# J65VIA.net
KiCad netlist of a schematic drawn in Altium Designer
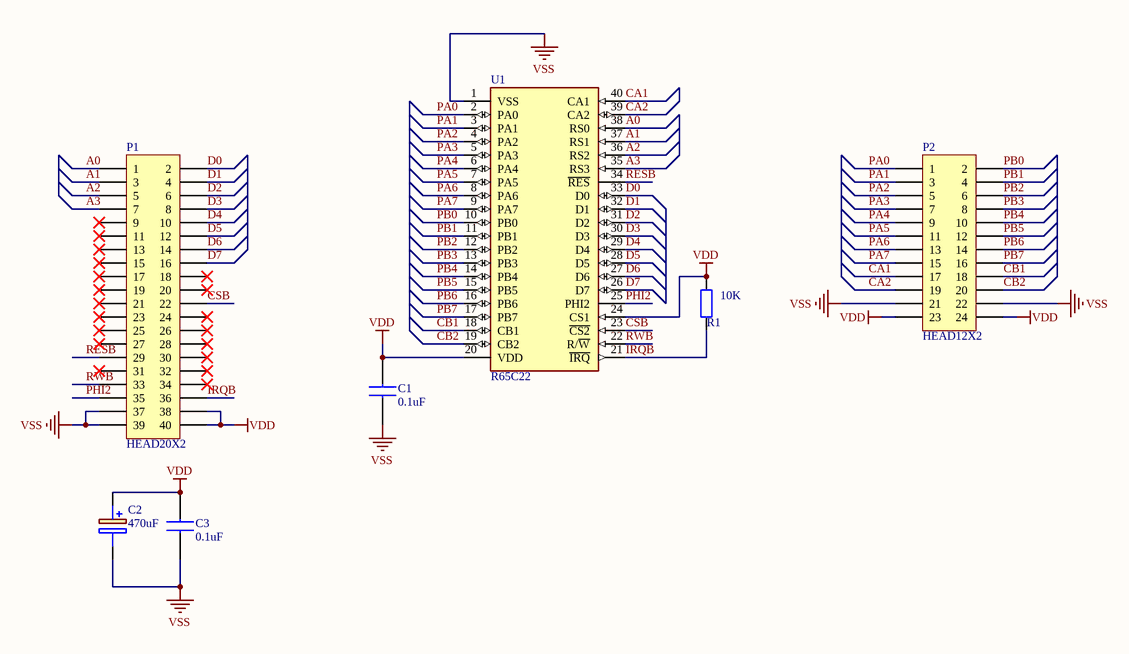
[diagram p0: J65VIA.SchDoc]

(export (version "E")
  (design (tool "Eeschema 10.0.6"))
  (components
    (comp (ref "C1") (value "0.1uF") (footprint "SamacSys:CAP508") (libsource (lib "SamacSys") (part "CAP1")))
    (comp (ref "C2")
      (value "470uF")
      (footprint "SamacSys:CAP8X12")
      (libsource (lib "SamacSys") (part "CAP2"))
    )
    (comp (ref "C3") (value "0.1uF") (footprint "SamacSys:CAP508") (libsource (lib "SamacSys") (part "CAP1")))
    (comp (ref "P1")
      (value "HEAD20X2")
      (footprint "HD20X2")
      (fields (field (name "PUBLISHER") "Altium Limited"))
      (libsource (lib "SamacSys") (part "HEAD20X2"))
    )
    (comp (ref "P2")
      (value "HEAD12X2")
      (footprint "HD12X2")
      (fields (field (name "PUBLISHER") "Altium Limited"))
      (libsource (lib "SamacSys") (part "HEAD12X2"))
    )
    (comp (ref "R1")
      (value "10K")
      (footprint "SamacSys:AXIAL-0.4")
      (libsource (lib "SamacSys") (part "RES1"))
    )
    (comp (ref "U1")
      (value "R65C22")
      (footprint "SamacSys:DIP40")
      (libsource (lib "SamacSys") (part "R65C22"))
    )
  )
  (nets
    (net (code "1") (name "/A0") (class "Default")
      (node (ref "P1") (pin "1") (pinfunction "1_1") (pintype "passive"))
      (node (ref "U1") (pin "38") (pinfunction "RS0_38") (pintype "input"))
    )
    (net (code "2") (name "/A1") (class "Default")
      (node (ref "P1") (pin "3") (pinfunction "3_3") (pintype "passive"))
      (node (ref "U1") (pin "37") (pinfunction "RS1_37") (pintype "input"))
    )
    (net (code "3") (name "/A2") (class "Default")
      (node (ref "P1") (pin "5") (pinfunction "5_5") (pintype "passive"))
      (node (ref "U1") (pin "36") (pinfunction "RS2_36") (pintype "input"))
    )
    (net (code "4") (name "/A3") (class "Default")
      (node (ref "P1") (pin "7") (pinfunction "7_7") (pintype "passive"))
      (node (ref "U1") (pin "35") (pinfunction "RS3_35") (pintype "input"))
    )
    (net (code "5") (name "/CA1") (class "Default")
      (node (ref "P2") (pin "17") (pinfunction "17_17") (pintype "passive"))
      (node (ref "U1") (pin "40") (pinfunction "CA1_40") (pintype "input"))
    )
    (net (code "6") (name "/CA2") (class "Default")
      (node (ref "P2") (pin "19") (pinfunction "19_19") (pintype "passive"))
      (node (ref "U1") (pin "39") (pinfunction "CA2_39") (pintype "bidirectional"))
    )
    (net (code "7") (name "/CB1") (class "Default")
      (node (ref "P2") (pin "18") (pinfunction "18_18") (pintype "passive"))
      (node (ref "U1") (pin "18") (pinfunction "CB1_18") (pintype "bidirectional"))
    )
    (net (code "8") (name "/CB2") (class "Default")
      (node (ref "P2") (pin "20") (pinfunction "20_20") (pintype "passive"))
      (node (ref "U1") (pin "19") (pinfunction "CB2_19") (pintype "bidirectional"))
    )
    (net (code "9") (name "/CSB") (class "Default")
      (node (ref "P1") (pin "22") (pinfunction "22_22") (pintype "passive"))
      (node (ref "U1") (pin "23") (pinfunction "~{CS2}_23") (pintype "input"))
    )
    (net (code "10") (name "/D0") (class "Default")
      (node (ref "P1") (pin "2") (pinfunction "2_2") (pintype "passive"))
      (node (ref "U1") (pin "33") (pinfunction "D0_33") (pintype "bidirectional"))
    )
    (net (code "11") (name "/D1") (class "Default")
      (node (ref "P1") (pin "4") (pinfunction "4_4") (pintype "passive"))
      (node (ref "U1") (pin "32") (pinfunction "D1_32") (pintype "bidirectional"))
    )
    (net (code "12") (name "/D2") (class "Default")
      (node (ref "P1") (pin "6") (pinfunction "6_6") (pintype "passive"))
      (node (ref "U1") (pin "31") (pinfunction "D2_31") (pintype "bidirectional"))
    )
    (net (code "13") (name "/D3") (class "Default")
      (node (ref "P1") (pin "8") (pinfunction "8_8") (pintype "passive"))
      (node (ref "U1") (pin "30") (pinfunction "D3_30") (pintype "bidirectional"))
    )
    (net (code "14") (name "/D4") (class "Default")
      (node (ref "P1") (pin "10") (pinfunction "10_10") (pintype "passive"))
      (node (ref "U1") (pin "29") (pinfunction "D4_29") (pintype "bidirectional"))
    )
    (net (code "15") (name "/D5") (class "Default")
      (node (ref "P1") (pin "12") (pinfunction "12_12") (pintype "passive"))
      (node (ref "U1") (pin "28") (pinfunction "D5_28") (pintype "bidirectional"))
    )
    (net (code "16") (name "/D6") (class "Default")
      (node (ref "P1") (pin "14") (pinfunction "14_14") (pintype "passive"))
      (node (ref "U1") (pin "27") (pinfunction "D6_27") (pintype "bidirectional"))
    )
    (net (code "17") (name "/D7") (class "Default")
      (node (ref "P1") (pin "16") (pinfunction "16_16") (pintype "passive"))
      (node (ref "U1") (pin "26") (pinfunction "D7_26") (pintype "bidirectional"))
    )
    (net (code "18") (name "/IRQB") (class "Default")
      (node (ref "P1") (pin "36") (pinfunction "36_36") (pintype "passive"))
      (node (ref "R1") (pin "2") (pinfunction "2_2") (pintype "passive"))
      (node (ref "U1") (pin "21") (pinfunction "~{IRQ}_21") (pintype "output"))
    )
    (net (code "19") (name "/PA0") (class "Default")
      (node (ref "P2") (pin "1") (pinfunction "1_1") (pintype "passive"))
      (node (ref "U1") (pin "2") (pinfunction "PA0_2") (pintype "bidirectional"))
    )
    (net (code "20") (name "/PA1") (class "Default")
      (node (ref "P2") (pin "3") (pinfunction "3_3") (pintype "passive"))
      (node (ref "U1") (pin "3") (pinfunction "PA1_3") (pintype "bidirectional"))
    )
    (net (code "21") (name "/PA2") (class "Default")
      (node (ref "P2") (pin "5") (pinfunction "5_5") (pintype "passive"))
      (node (ref "U1") (pin "4") (pinfunction "PA2_4") (pintype "bidirectional"))
    )
    (net (code "22") (name "/PA3") (class "Default")
      (node (ref "P2") (pin "7") (pinfunction "7_7") (pintype "passive"))
      (node (ref "U1") (pin "5") (pinfunction "PA3_5") (pintype "bidirectional"))
    )
    (net (code "23") (name "/PA4") (class "Default")
      (node (ref "P2") (pin "9") (pinfunction "9_9") (pintype "passive"))
      (node (ref "U1") (pin "6") (pinfunction "PA4_6") (pintype "bidirectional"))
    )
    (net (code "24") (name "/PA5") (class "Default")
      (node (ref "P2") (pin "11") (pinfunction "11_11") (pintype "passive"))
      (node (ref "U1") (pin "7") (pinfunction "PA5_7") (pintype "bidirectional"))
    )
    (net (code "25") (name "/PA6") (class "Default")
      (node (ref "P2") (pin "13") (pinfunction "13_13") (pintype "passive"))
      (node (ref "U1") (pin "8") (pinfunction "PA6_8") (pintype "bidirectional"))
    )
    (net (code "26") (name "/PA7") (class "Default")
      (node (ref "P2") (pin "15") (pinfunction "15_15") (pintype "passive"))
      (node (ref "U1") (pin "9") (pinfunction "PA7_9") (pintype "bidirectional"))
    )
    (net (code "27") (name "/PB0") (class "Default")
      (node (ref "P2") (pin "2") (pinfunction "2_2") (pintype "passive"))
      (node (ref "U1") (pin "10") (pinfunction "PB0_10") (pintype "bidirectional"))
    )
    (net (code "28") (name "/PB1") (class "Default")
      (node (ref "P2") (pin "4") (pinfunction "4_4") (pintype "passive"))
      (node (ref "U1") (pin "11") (pinfunction "PB1_11") (pintype "bidirectional"))
    )
    (net (code "29") (name "/PB2") (class "Default")
      (node (ref "P2") (pin "6") (pinfunction "6_6") (pintype "passive"))
      (node (ref "U1") (pin "12") (pinfunction "PB2_12") (pintype "bidirectional"))
    )
    (net (code "30") (name "/PB3") (class "Default")
      (node (ref "P2") (pin "8") (pinfunction "8_8") (pintype "passive"))
      (node (ref "U1") (pin "13") (pinfunction "PB3_13") (pintype "bidirectional"))
    )
    (net (code "31") (name "/PB4") (class "Default")
      (node (ref "P2") (pin "10") (pinfunction "10_10") (pintype "passive"))
      (node (ref "U1") (pin "14") (pinfunction "PB4_14") (pintype "bidirectional"))
    )
    (net (code "32") (name "/PB5") (class "Default")
      (node (ref "P2") (pin "12") (pinfunction "12_12") (pintype "passive"))
      (node (ref "U1") (pin "15") (pinfunction "PB5_15") (pintype "bidirectional"))
    )
    (net (code "33") (name "/PB6") (class "Default")
      (node (ref "P2") (pin "14") (pinfunction "14_14") (pintype "passive"))
      (node (ref "U1") (pin "16") (pinfunction "PB6_16") (pintype "bidirectional"))
    )
    (net (code "34") (name "/PB7") (class "Default")
      (node (ref "P2") (pin "16") (pinfunction "16_16") (pintype "passive"))
      (node (ref "U1") (pin "17") (pinfunction "PB7_17") (pintype "bidirectional"))
    )
    (net (code "35") (name "/PHI2") (class "Default")
      (node (ref "P1") (pin "35") (pinfunction "35_35") (pintype "passive"))
      (node (ref "U1") (pin "25") (pinfunction "PHI2_25") (pintype "passive"))
    )
    (net (code "36") (name "/RESB") (class "Default")
      (node (ref "P1") (pin "29") (pinfunction "29_29") (pintype "passive"))
      (node (ref "U1") (pin "34") (pinfunction "~{RES}_34") (pintype "passive"))
    )
    (net (code "37") (name "/RWB") (class "Default")
      (node (ref "P1") (pin "33") (pinfunction "33_33") (pintype "passive"))
      (node (ref "U1") (pin "22") (pinfunction "R/~{W}_22") (pintype "input"))
    )
    (net (code "38") (name "VDD") (class "Default")
      (node (ref "C1") (pin "1") (pinfunction "1_1") (pintype "passive"))
      (node (ref "C2") (pin "1") (pinfunction "+_1") (pintype "passive"))
      (node (ref "C3") (pin "1") (pinfunction "1_1") (pintype "passive"))
      (node (ref "P1") (pin "38") (pinfunction "38_38") (pintype "passive"))
      (node (ref "P1") (pin "40") (pinfunction "40_40") (pintype "passive"))
      (node (ref "P2") (pin "23") (pinfunction "23_23") (pintype "passive"))
      (node (ref "P2") (pin "24") (pinfunction "24_24") (pintype "passive"))
      (node (ref "R1") (pin "1") (pinfunction "1_1") (pintype "passive"))
      (node (ref "U1") (pin "20") (pinfunction "VDD_20") (pintype "passive"))
      (node (ref "U1") (pin "24") (pinfunction "CS1_24") (pintype "input"))
    )
    (net (code "39") (name "VSS") (class "Default")
      (node (ref "C1") (pin "2") (pinfunction "2_2") (pintype "passive"))
      (node (ref "C2") (pin "2") (pinfunction "-_2") (pintype "passive"))
      (node (ref "C3") (pin "2") (pinfunction "2_2") (pintype "passive"))
      (node (ref "P1") (pin "37") (pinfunction "37_37") (pintype "passive"))
      (node (ref "P1") (pin "39") (pinfunction "39_39") (pintype "passive"))
      (node (ref "P2") (pin "21") (pinfunction "21_21") (pintype "passive"))
      (node (ref "P2") (pin "22") (pinfunction "22_22") (pintype "passive"))
      (node (ref "U1") (pin "1") (pinfunction "VSS_1") (pintype "passive"))
    )
    (net (code "40") (name "unconnected-(P1-Pad9)") (class "Default")
      (node (ref "P1") (pin "9") (pinfunction "9_9") (pintype "passive+no_connect"))
    )
    (net (code "41") (name "unconnected-(P1-Pad11)") (class "Default")
      (node (ref "P1") (pin "11") (pinfunction "11_11") (pintype "passive+no_connect"))
    )
    (net (code "42") (name "unconnected-(P1-Pad13)") (class "Default")
      (node (ref "P1") (pin "13") (pinfunction "13_13") (pintype "passive+no_connect"))
    )
    (net (code "43") (name "unconnected-(P1-Pad15)") (class "Default")
      (node (ref "P1") (pin "15") (pinfunction "15_15") (pintype "passive+no_connect"))
    )
    (net (code "44") (name "unconnected-(P1-Pad17)") (class "Default")
      (node (ref "P1") (pin "17") (pinfunction "17_17") (pintype "passive+no_connect"))
    )
    (net (code "45") (name "unconnected-(P1-Pad18)") (class "Default")
      (node (ref "P1") (pin "18") (pinfunction "18_18") (pintype "passive+no_connect"))
    )
    (net (code "46") (name "unconnected-(P1-Pad19)") (class "Default")
      (node (ref "P1") (pin "19") (pinfunction "19_19") (pintype "passive+no_connect"))
    )
    (net (code "47") (name "unconnected-(P1-Pad20)") (class "Default")
      (node (ref "P1") (pin "20") (pinfunction "20_20") (pintype "passive+no_connect"))
    )
    (net (code "48") (name "unconnected-(P1-Pad21)") (class "Default")
      (node (ref "P1") (pin "21") (pinfunction "21_21") (pintype "passive+no_connect"))
    )
    (net (code "49") (name "unconnected-(P1-Pad23)") (class "Default")
      (node (ref "P1") (pin "23") (pinfunction "23_23") (pintype "passive+no_connect"))
    )
    (net (code "50") (name "unconnected-(P1-Pad24)") (class "Default")
      (node (ref "P1") (pin "24") (pinfunction "24_24") (pintype "passive+no_connect"))
    )
    (net (code "51") (name "unconnected-(P1-Pad25)") (class "Default")
      (node (ref "P1") (pin "25") (pinfunction "25_25") (pintype "passive+no_connect"))
    )
    (net (code "52") (name "unconnected-(P1-Pad26)") (class "Default")
      (node (ref "P1") (pin "26") (pinfunction "26_26") (pintype "passive+no_connect"))
    )
    (net (code "53") (name "unconnected-(P1-Pad27)") (class "Default")
      (node (ref "P1") (pin "27") (pinfunction "27_27") (pintype "passive+no_connect"))
    )
    (net (code "54") (name "unconnected-(P1-Pad28)") (class "Default")
      (node (ref "P1") (pin "28") (pinfunction "28_28") (pintype "passive+no_connect"))
    )
    (net (code "55") (name "unconnected-(P1-Pad30)") (class "Default")
      (node (ref "P1") (pin "30") (pinfunction "30_30") (pintype "passive+no_connect"))
    )
    (net (code "56") (name "unconnected-(P1-Pad31)") (class "Default")
      (node (ref "P1") (pin "31") (pinfunction "31_31") (pintype "passive+no_connect"))
    )
    (net (code "57") (name "unconnected-(P1-Pad32)") (class "Default")
      (node (ref "P1") (pin "32") (pinfunction "32_32") (pintype "passive+no_connect"))
    )
    (net (code "58") (name "unconnected-(P1-Pad34)") (class "Default")
      (node (ref "P1") (pin "34") (pinfunction "34_34") (pintype "passive+no_connect"))
    )
  )
)
